# SKC_DataComm.net
KiCad netlist of a schematic drawn in Altium Designer
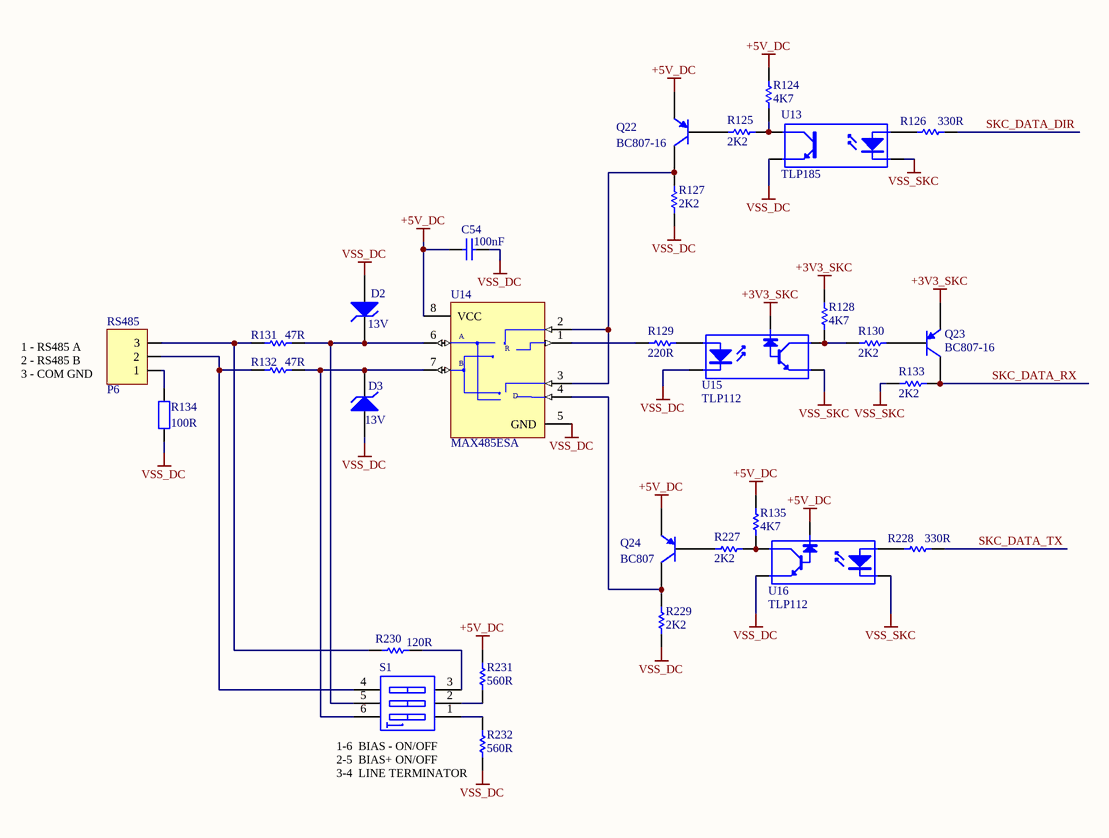
[diagram p0: SKC_DataComm.SchDoc]

(export (version "E")
  (design (tool "Eeschema 10.0.6"))
  (components
    (comp (ref "C54")
      (value "100nF")
      (footprint "1206")
      (description "Ceramic Chip Capacitor - Standard")
      (fields (field (name "PUBLISHER") "Altium Limited"))
      (libsource (lib "KEMET Chip Capacitor") (part "C1206"))
    )
    (comp (ref "D2")
      (value "13V")
      (footprint "Miscellaneous Devices:DO-35A")
      (description "Zener Diode")
      (fields (field (name "PUBLISHER") "Altium Limited"))
      (libsource (lib "Miscellaneous Devices") (part "D Zener"))
    )
    (comp (ref "D3")
      (value "13V")
      (footprint "Miscellaneous Devices:DO-35A")
      (description "Zener Diode")
      (fields (field (name "PUBLISHER") "Altium Limited"))
      (libsource (lib "Miscellaneous Devices") (part "D Zener"))
    )
    (comp (ref "P6")
      (value "RS485")
      (footprint "TERMINAL BLOK 3")
      (description "3 pinski terminal blok konektor")
      (libsource (lib "ProjectLibrary") (part "TERMINAL BLOK 3"))
    )
    (comp (ref "Q22")
      (value "BC807-16")
      (footprint "SOT23_N")
      (description "PNP General-purpose Transistor")
      (fields (field (name "PUBLISHER") "Altium Limited"))
      (libsource (lib "Philips Discrete BJT - Low Power") (part "BC807-16"))
    )
    (comp (ref "Q23")
      (value "BC807-16")
      (footprint "SOT23_N")
      (description "PNP General-purpose Transistor")
      (fields (field (name "PUBLISHER") "Altium Limited"))
      (libsource (lib "Philips Discrete BJT - Low Power") (part "BC807-16"))
    )
    (comp (ref "Q24")
      (value "BC807")
      (footprint "SOT23_N")
      (description "PNP General-purpose Transistor")
      (fields (field (name "PUBLISHER") "Altium Limited"))
      (libsource (lib "Philips Discrete BJT - Low Power") (part "BC807-16"))
    )
    (comp (ref "R124")
      (value "4K7")
      (footprint "ERA-0805")
      (fields (field (name "PUBLISHER") "Altium Limited"))
      (libsource (lib "Panasonic Resistor") (part "ERAS"))
    )
    (comp (ref "R125")
      (value "2K2")
      (footprint "ERA-0805")
      (fields (field (name "PUBLISHER") "Altium Limited"))
      (libsource (lib "Panasonic Resistor") (part "ERAS"))
    )
    (comp (ref "R126")
      (value "330R")
      (footprint "ERA-0805")
      (fields (field (name "PUBLISHER") "Altium Limited"))
      (libsource (lib "Panasonic Resistor") (part "ERA6Y"))
    )
    (comp (ref "R127")
      (value "2K2")
      (footprint "8-1206")
      (description "Thick Film Chip Resistor, 1 Ohm to 10M Ohm Range, 5% Tolerance, 1206 Size, 0.25 W")
      (fields (field (name "PUBLISHER") "Altium Limited"))
      (libsource (lib "Panasonic Resistor") (part "ERJ8GE"))
    )
    (comp (ref "R128")
      (value "4K7")
      (footprint "ERA-0805")
      (fields (field (name "PUBLISHER") "Altium Limited"))
      (libsource (lib "Panasonic Resistor") (part "ERAS"))
    )
    (comp (ref "R129")
      (value "220R")
      (footprint "ERA-0805")
      (fields (field (name "PUBLISHER") "Altium Limited"))
      (libsource (lib "Panasonic Resistor") (part "ERAS"))
    )
    (comp (ref "R130")
      (value "2K2")
      (footprint "ERA-0805")
      (fields (field (name "PUBLISHER") "Altium Limited"))
      (libsource (lib "Panasonic Resistor") (part "ERAS"))
    )
    (comp (ref "R131")
      (value "47R")
      (footprint "ERA-0805")
      (fields (field (name "PUBLISHER") "Altium Limited"))
      (libsource (lib "Panasonic Resistor") (part "ERAS"))
    )
    (comp (ref "R132")
      (value "47R")
      (footprint "ERA-0805")
      (fields (field (name "PUBLISHER") "Altium Limited"))
      (libsource (lib "Panasonic Resistor") (part "ERAS"))
    )
    (comp (ref "R133")
      (value "2K2")
      (footprint "8-1206")
      (description "Thick Film Chip Resistor, 1 Ohm to 10M Ohm Range, 5% Tolerance, 1206 Size, 0.25 W")
      (fields (field (name "PUBLISHER") "Altium Limited"))
      (libsource (lib "Panasonic Resistor") (part "ERJ8GE"))
    )
    (comp (ref "R134")
      (value "100R")
      (footprint "AXIAL-0.4")
      (description "Resistor")
      (fields (field (name "PUBLISHER") "Altium Limited"))
      (libsource (lib "Miscellaneous Devices") (part "Res2"))
    )
    (comp (ref "R135")
      (value "4K7")
      (footprint "ERA-0805")
      (fields (field (name "PUBLISHER") "Altium Limited"))
      (libsource (lib "Panasonic Resistor") (part "ERAS"))
    )
    (comp (ref "R227")
      (value "2K2")
      (footprint "8-1206")
      (description "Thick Film Chip Resistor, 1 Ohm to 10M Ohm Range, 5% Tolerance, 1206 Size, 0.25 W")
      (fields (field (name "PUBLISHER") "Altium Limited"))
      (libsource (lib "Panasonic Resistor") (part "ERJ8GE"))
    )
    (comp (ref "R228")
      (value "330R")
      (footprint "ERA-0805")
      (fields (field (name "PUBLISHER") "Altium Limited"))
      (libsource (lib "Panasonic Resistor") (part "ERA6Y"))
    )
    (comp (ref "R229")
      (value "2K2")
      (footprint "8-1206")
      (description "Thick Film Chip Resistor, 1 Ohm to 10M Ohm Range, 5% Tolerance, 1206 Size, 0.25 W")
      (fields (field (name "PUBLISHER") "Altium Limited"))
      (libsource (lib "Panasonic Resistor") (part "ERJ8GE"))
    )
    (comp (ref "R230")
      (value "120R")
      (footprint "ERA-0805")
      (fields (field (name "PUBLISHER") "Altium Limited"))
      (libsource (lib "Panasonic Resistor") (part "ERAS"))
    )
    (comp (ref "R231")
      (value "560R")
      (footprint "ERA-0805")
      (fields (field (name "PUBLISHER") "Altium Limited"))
      (libsource (lib "Panasonic Resistor") (part "ERAS"))
    )
    (comp (ref "R232")
      (value "560R")
      (footprint "ERA-0805")
      (fields (field (name "PUBLISHER") "Altium Limited"))
      (libsource (lib "Panasonic Resistor") (part "ERAS"))
    )
    (comp (ref "S1")
      (value "~")
      (footprint "DIP-6")
      (description "DIP Switch, 3 Position, SPST")
      (fields (field (name "PUBLISHER") "Altium Limited"))
      (libsource (lib "Miscellaneous Devices") (part "SW DIP-3"))
    )
    (comp (ref "U13")
      (value "TLP185")
      (footprint "SOP4")
      (description "4 Pin Mini Flat Pack Optocoupler")
      (fields (field (name "PUBLISHER") "Altium Limited"))
      (libsource (lib "ProjectLibrary") (part "TLP185"))
    )
    (comp (ref "U14")
      (value "MAX485ESA")
      (footprint "NSO8_N")
      (description "Low-Power, Slew-Rate-Limited RS-485/RS-422 Transceiver")
      (fields (field (name "PUBLISHER") "Altium Limited"))
      (libsource (lib "Maxim Communication Transceiver") (part "MAX485ESA"))
    )
    (comp (ref "U15")
      (value "TLP112")
      (footprint "SOP5")
      (description "5 Pin Mini Flat Pack Optocoupler")
      (fields (field (name "PUBLISHER") "Altium Limited"))
      (libsource (lib "ProjectLibrary") (part "TLP112"))
    )
    (comp (ref "U16")
      (value "TLP112")
      (footprint "SOP5")
      (description "5 Pin Mini Flat Pack Optocoupler")
      (fields (field (name "PUBLISHER") "Altium Limited"))
      (libsource (lib "") (part "TLP112_1"))
    )
  )
  (nets
    (net (code "1") (name "+3V3_SKC") (class "Default")
      (node (ref "Q23") (pin "2") (pinfunction "E_2") (pintype "passive"))
      (node (ref "R128") (pin "1") (pinfunction "1_1") (pintype "passive"))
      (node (ref "U15") (pin "6") (pinfunction "K_6") (pintype "passive"))
    )
    (net (code "2") (name "+5V_DC") (class "Default")
      (node (ref "C54") (pin "2") (pinfunction "2_2") (pintype "passive"))
      (node (ref "Q22") (pin "2") (pinfunction "E_2") (pintype "passive"))
      (node (ref "Q24") (pin "2") (pinfunction "E_2") (pintype "passive"))
      (node (ref "R124") (pin "1") (pinfunction "1_1") (pintype "passive"))
      (node (ref "R135") (pin "1") (pinfunction "1_1") (pintype "passive"))
      (node (ref "R231") (pin "2") (pinfunction "2_2") (pintype "passive"))
      (node (ref "U14") (pin "8") (pinfunction "VCC_8") (pintype "power_in"))
      (node (ref "U16") (pin "6") (pinfunction "K_6") (pintype "passive"))
    )
    (net (code "3") (name "/SKC_DATA_DIR") (class "Default")
      (node (ref "R126") (pin "2") (pinfunction "2_2") (pintype "passive"))
    )
    (net (code "4") (name "/SKC_DATA_RX") (class "Default")
      (node (ref "Q23") (pin "3") (pinfunction "C_3") (pintype "passive"))
      (node (ref "R133") (pin "2") (pinfunction "2_2") (pintype "passive"))
    )
    (net (code "5") (name "/SKC_DATA_TX") (class "Default")
      (node (ref "R228") (pin "2") (pinfunction "2_2") (pintype "passive"))
    )
    (net (code "6") (name "Net-(D2-K)") (class "Default")
      (node (ref "D2") (pin "2") (pinfunction "K_2") (pintype "passive"))
      (node (ref "R131") (pin "2") (pinfunction "2_2") (pintype "passive"))
      (node (ref "S1") (pin "5") (pinfunction "B2_5") (pintype "passive"))
      (node (ref "U14") (pin "6") (pinfunction "A_6") (pintype "bidirectional"))
    )
    (net (code "7") (name "Net-(D3-K)") (class "Default")
      (node (ref "D3") (pin "2") (pinfunction "K_2") (pintype "passive"))
      (node (ref "R132") (pin "2") (pinfunction "2_2") (pintype "passive"))
      (node (ref "S1") (pin "6") (pinfunction "B1_6") (pintype "passive"))
      (node (ref "U14") (pin "7") (pinfunction "B_7") (pintype "bidirectional"))
    )
    (net (code "8") (name "Net-(P6-Pad1)") (class "Default")
      (node (ref "P6") (pin "1") (pinfunction "1_1") (pintype "passive"))
      (node (ref "R134") (pin "2") (pinfunction "2_2") (pintype "passive"))
    )
    (net (code "9") (name "Net-(P6-Pad3)") (class "Default")
      (node (ref "P6") (pin "3") (pinfunction "3_3") (pintype "passive"))
      (node (ref "R131") (pin "1") (pinfunction "1_1") (pintype "passive"))
      (node (ref "R230") (pin "1") (pinfunction "1_1") (pintype "passive"))
    )
    (net (code "10") (name "Net-(Q22-B)") (class "Default")
      (node (ref "Q22") (pin "1") (pinfunction "B_1") (pintype "passive"))
      (node (ref "R125") (pin "2") (pinfunction "2_2") (pintype "passive"))
    )
    (net (code "11") (name "Net-(Q22-C)") (class "Default")
      (node (ref "Q22") (pin "3") (pinfunction "C_3") (pintype "passive"))
      (node (ref "R127") (pin "2") (pinfunction "2_2") (pintype "passive"))
      (node (ref "U14") (pin "2") (pinfunction "~{RE}_2") (pintype "input"))
      (node (ref "U14") (pin "3") (pinfunction "DE_3") (pintype "input"))
    )
    (net (code "12") (name "Net-(Q23-B)") (class "Default")
      (node (ref "Q23") (pin "1") (pinfunction "B_1") (pintype "passive"))
      (node (ref "R130") (pin "1") (pinfunction "1_1") (pintype "passive"))
    )
    (net (code "13") (name "Net-(Q24-B)") (class "Default")
      (node (ref "Q24") (pin "1") (pinfunction "B_1") (pintype "passive"))
      (node (ref "R227") (pin "2") (pinfunction "2_2") (pintype "passive"))
    )
    (net (code "14") (name "Net-(Q24-C)") (class "Default")
      (node (ref "Q24") (pin "3") (pinfunction "C_3") (pintype "passive"))
      (node (ref "R229") (pin "2") (pinfunction "2_2") (pintype "passive"))
      (node (ref "U14") (pin "4") (pinfunction "DI_4") (pintype "input"))
    )
    (net (code "15") (name "Net-(S1-A1)") (class "Default")
      (node (ref "R232") (pin "2") (pinfunction "2_2") (pintype "passive"))
      (node (ref "S1") (pin "1") (pinfunction "A1_1") (pintype "passive"))
    )
    (net (code "16") (name "Net-(S1-A2)") (class "Default")
      (node (ref "R231") (pin "1") (pinfunction "1_1") (pintype "passive"))
      (node (ref "S1") (pin "2") (pinfunction "A2_2") (pintype "passive"))
    )
    (net (code "17") (name "Net-(S1-A3)") (class "Default")
      (node (ref "R230") (pin "2") (pinfunction "2_2") (pintype "passive"))
      (node (ref "S1") (pin "3") (pinfunction "A3_3") (pintype "passive"))
    )
    (net (code "18") (name "Net-(S1-B3)") (class "Default")
      (node (ref "P6") (pin "2") (pinfunction "2_2") (pintype "passive"))
      (node (ref "R132") (pin "1") (pinfunction "1_1") (pintype "passive"))
      (node (ref "S1") (pin "4") (pinfunction "B3_4") (pintype "passive"))
    )
    (net (code "19") (name "Net-(U13-A)") (class "Default")
      (node (ref "R126") (pin "1") (pinfunction "1_1") (pintype "passive"))
      (node (ref "U13") (pin "1") (pinfunction "A_1") (pintype "passive"))
    )
    (net (code "20") (name "Net-(U13-C)") (class "Default")
      (node (ref "R124") (pin "2") (pinfunction "2_2") (pintype "passive"))
      (node (ref "R125") (pin "1") (pinfunction "1_1") (pintype "passive"))
      (node (ref "U13") (pin "6") (pinfunction "C_6") (pintype "passive"))
    )
    (net (code "21") (name "Net-(U14-RO)") (class "Default")
      (node (ref "R129") (pin "2") (pinfunction "2_2") (pintype "passive"))
      (node (ref "U14") (pin "1") (pinfunction "RO_1") (pintype "output"))
    )
    (net (code "22") (name "Net-(U15-A)") (class "Default")
      (node (ref "R129") (pin "1") (pinfunction "1_1") (pintype "passive"))
      (node (ref "U15") (pin "1") (pinfunction "A_1") (pintype "passive"))
    )
    (net (code "23") (name "Net-(U15-C)") (class "Default")
      (node (ref "R128") (pin "2") (pinfunction "2_2") (pintype "passive"))
      (node (ref "R130") (pin "2") (pinfunction "2_2") (pintype "passive"))
      (node (ref "U15") (pin "5") (pinfunction "C_5") (pintype "passive"))
    )
    (net (code "24") (name "Net-(U16-A)") (class "Default")
      (node (ref "R228") (pin "1") (pinfunction "1_1") (pintype "passive"))
      (node (ref "U16") (pin "1") (pinfunction "A_1") (pintype "passive"))
    )
    (net (code "25") (name "Net-(U16-C)") (class "Default")
      (node (ref "R135") (pin "2") (pinfunction "2_2") (pintype "passive"))
      (node (ref "R227") (pin "1") (pinfunction "1_1") (pintype "passive"))
      (node (ref "U16") (pin "5") (pinfunction "C_5") (pintype "passive"))
    )
    (net (code "26") (name "VSS_DC") (class "Default")
      (node (ref "C54") (pin "1") (pinfunction "1_1") (pintype "passive"))
      (node (ref "D2") (pin "1") (pinfunction "A_1") (pintype "passive"))
      (node (ref "D3") (pin "1") (pinfunction "A_1") (pintype "passive"))
      (node (ref "R127") (pin "1") (pinfunction "1_1") (pintype "passive"))
      (node (ref "R134") (pin "1") (pinfunction "1_1") (pintype "passive"))
      (node (ref "R229") (pin "1") (pinfunction "1_1") (pintype "passive"))
      (node (ref "R232") (pin "1") (pinfunction "1_1") (pintype "passive"))
      (node (ref "U13") (pin "4") (pinfunction "E_4") (pintype "passive"))
      (node (ref "U14") (pin "5") (pinfunction "GND_5") (pintype "power_in"))
      (node (ref "U15") (pin "3") (pinfunction "K_3") (pintype "passive"))
      (node (ref "U16") (pin "4") (pinfunction "E_4") (pintype "passive"))
    )
    (net (code "27") (name "VSS_SKC") (class "Default")
      (node (ref "R133") (pin "1") (pinfunction "1_1") (pintype "passive"))
      (node (ref "U13") (pin "3") (pinfunction "K_3") (pintype "passive"))
      (node (ref "U15") (pin "4") (pinfunction "E_4") (pintype "passive"))
      (node (ref "U16") (pin "3") (pinfunction "K_3") (pintype "passive"))
    )
  )
)
